# StepperMotor1CTRL.net
KiCad netlist of a schematic drawn in Altium Designer
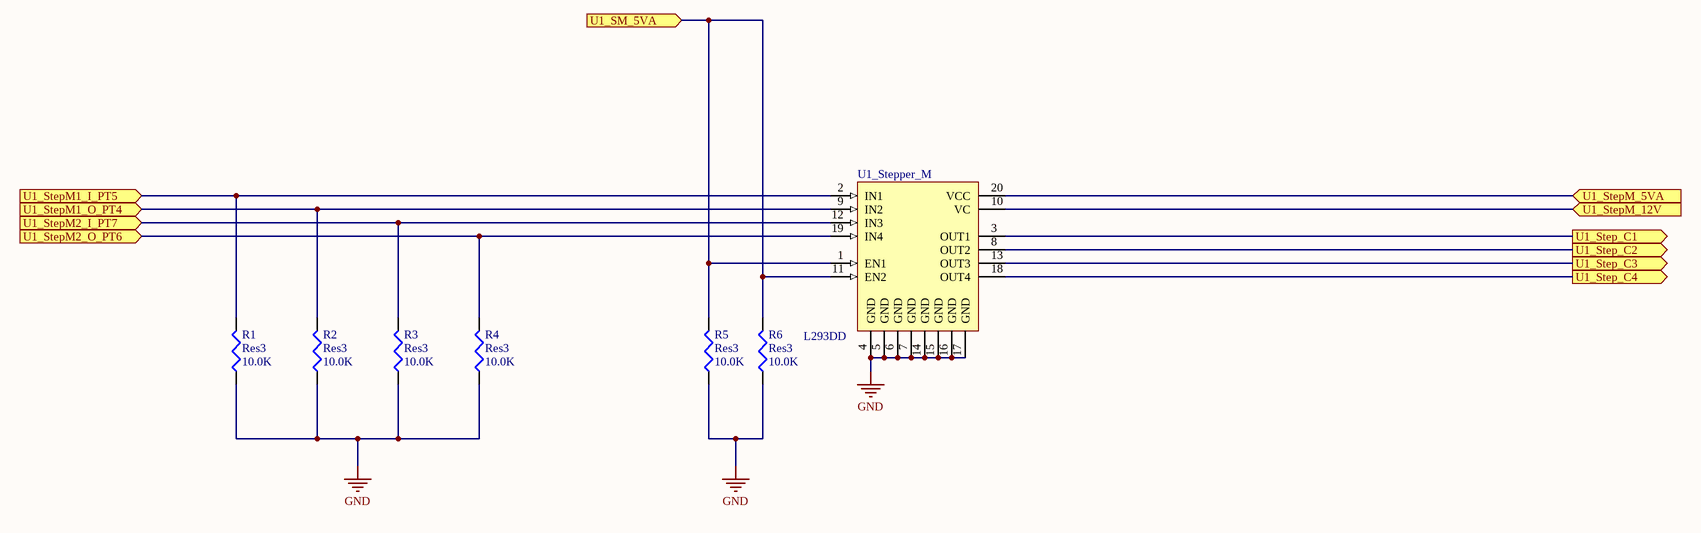
[diagram p0: StepperMotor1CTRL.SchDoc]

(export (version "E")
  (design (tool "Eeschema 10.0.6"))
  (components
    (comp (ref "R1")
      (value "Res3")
      (footprint "RESC2112X05M")
      (description "RES SMD 10.0K OHM 1% 1/8W 0805")
      (fields (field (name "ALTIUM_VALUE") "10.0K") (field (name "MPN") "CRCW080510K0FKEA"))
      (libsource (lib "esd_library") (part "Resistor_10.0K"))
    )
    (comp (ref "R2")
      (value "Res3")
      (footprint "RESC2112X05M")
      (description "RES SMD 10.0K OHM 1% 1/8W 0805")
      (fields (field (name "ALTIUM_VALUE") "10.0K") (field (name "MPN") "CRCW080510K0FKEA"))
      (libsource (lib "esd_library") (part "Resistor_10.0K"))
    )
    (comp (ref "R3")
      (value "Res3")
      (footprint "RESC2112X05M")
      (description "RES SMD 10.0K OHM 1% 1/8W 0805")
      (fields (field (name "ALTIUM_VALUE") "10.0K") (field (name "MPN") "CRCW080510K0FKEA"))
      (libsource (lib "esd_library") (part "Resistor_10.0K"))
    )
    (comp (ref "R4")
      (value "Res3")
      (footprint "RESC2112X05M")
      (description "RES SMD 10.0K OHM 1% 1/8W 0805")
      (fields (field (name "ALTIUM_VALUE") "10.0K") (field (name "MPN") "CRCW080510K0FKEA"))
      (libsource (lib "esd_library") (part "Resistor_10.0K"))
    )
    (comp (ref "R5")
      (value "Res3")
      (footprint "RESC2112X05M")
      (description "RES SMD 10.0K OHM 1% 1/8W 0805")
      (fields (field (name "ALTIUM_VALUE") "10.0K") (field (name "MPN") "CRCW080510K0FKEA"))
      (libsource (lib "esd_library") (part "Resistor_10.0K"))
    )
    (comp (ref "R6")
      (value "Res3")
      (footprint "RESC2112X05M")
      (description "RES SMD 10.0K OHM 1% 1/8W 0805")
      (fields (field (name "ALTIUM_VALUE") "10.0K") (field (name "MPN") "CRCW080510K0FKEA"))
      (libsource (lib "esd_library") (part "Resistor_10.0K"))
    )
    (comp (ref "U1_Stepper_M")
      (value "L293DD")
      (footprint "SO20_N")
      (description "Push-Pull Four Channel Driver With Diode")
      (fields (field (name "PUBLISHER") "Altium Limited"))
      (libsource (lib "esd_library") (part "L293DD"))
    )
  )
  (nets
    (net (code "1") (name "/U1_SM_5VA") (class "Default")
      (node (ref "R5") (pin "2") (pinfunction "2_2") (pintype "passive"))
      (node (ref "R6") (pin "2") (pinfunction "2_2") (pintype "passive"))
      (node (ref "U1_Stepper_M") (pin "1") (pinfunction "EN1_1") (pintype "input"))
      (node (ref "U1_Stepper_M") (pin "11") (pinfunction "EN2_11") (pintype "input"))
    )
    (net (code "2") (name "/U1_StepM1_I_PT5") (class "Default")
      (node (ref "R1") (pin "2") (pinfunction "2_2") (pintype "passive"))
      (node (ref "U1_Stepper_M") (pin "2") (pinfunction "IN1_2") (pintype "input"))
    )
    (net (code "3") (name "/U1_StepM1_O_PT4") (class "Default")
      (node (ref "R2") (pin "2") (pinfunction "2_2") (pintype "passive"))
      (node (ref "U1_Stepper_M") (pin "9") (pinfunction "IN2_9") (pintype "input"))
    )
    (net (code "4") (name "/U1_StepM2_I_PT7") (class "Default")
      (node (ref "R3") (pin "2") (pinfunction "2_2") (pintype "passive"))
      (node (ref "U1_Stepper_M") (pin "12") (pinfunction "IN3_12") (pintype "input"))
    )
    (net (code "5") (name "/U1_StepM2_O_PT6") (class "Default")
      (node (ref "R4") (pin "2") (pinfunction "2_2") (pintype "passive"))
      (node (ref "U1_Stepper_M") (pin "19") (pinfunction "IN4_19") (pintype "input"))
    )
    (net (code "6") (name "/U1_StepM_5VA") (class "Default")
      (node (ref "U1_Stepper_M") (pin "20") (pinfunction "VCC_20") (pintype "power_in"))
    )
    (net (code "7") (name "/U1_StepM_12V") (class "Default")
      (node (ref "U1_Stepper_M") (pin "10") (pinfunction "VC_10") (pintype "power_in"))
    )
    (net (code "8") (name "/U1_Step_C1") (class "Default")
      (node (ref "U1_Stepper_M") (pin "3") (pinfunction "OUT1_3") (pintype "tri_state"))
    )
    (net (code "9") (name "/U1_Step_C2") (class "Default")
      (node (ref "U1_Stepper_M") (pin "8") (pinfunction "OUT2_8") (pintype "tri_state"))
    )
    (net (code "10") (name "/U1_Step_C3") (class "Default")
      (node (ref "U1_Stepper_M") (pin "13") (pinfunction "OUT3_13") (pintype "tri_state"))
    )
    (net (code "11") (name "/U1_Step_C4") (class "Default")
      (node (ref "U1_Stepper_M") (pin "18") (pinfunction "OUT4_18") (pintype "tri_state"))
    )
    (net (code "12") (name "GND") (class "Default")
      (node (ref "R1") (pin "1") (pinfunction "1_1") (pintype "passive"))
      (node (ref "R2") (pin "1") (pinfunction "1_1") (pintype "passive"))
      (node (ref "R3") (pin "1") (pinfunction "1_1") (pintype "passive"))
      (node (ref "R4") (pin "1") (pinfunction "1_1") (pintype "passive"))
      (node (ref "R5") (pin "1") (pinfunction "1_1") (pintype "passive"))
      (node (ref "R6") (pin "1") (pinfunction "1_1") (pintype "passive"))
      (node (ref "U1_Stepper_M") (pin "14") (pinfunction "GND_14") (pintype "power_in"))
      (node (ref "U1_Stepper_M") (pin "15") (pinfunction "GND_15") (pintype "power_in"))
      (node (ref "U1_Stepper_M") (pin "16") (pinfunction "GND_16") (pintype "power_in"))
      (node (ref "U1_Stepper_M") (pin "17") (pinfunction "GND_17") (pintype "power_in"))
      (node (ref "U1_Stepper_M") (pin "4") (pinfunction "GND_4") (pintype "power_in"))
      (node (ref "U1_Stepper_M") (pin "5") (pinfunction "GND_5") (pintype "power_in"))
      (node (ref "U1_Stepper_M") (pin "6") (pinfunction "GND_6") (pintype "power_in"))
      (node (ref "U1_Stepper_M") (pin "7") (pinfunction "GND_7") (pintype "power_in"))
    )
  )
)
